# VoltageBooster48V.net
KiCad netlist of a schematic drawn in Altium Designer
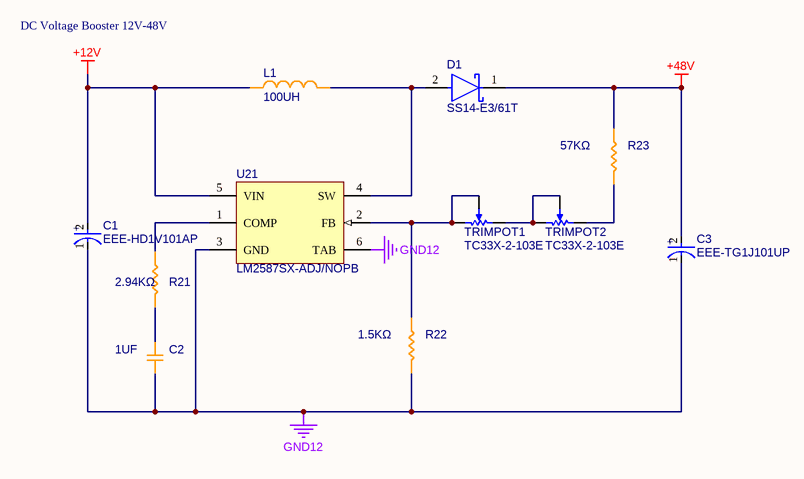
[diagram p0: VoltageBooster48V.SchDoc]

(export (version "E")
  (design (tool "Eeschema 10.0.6"))
  (components
    (comp (ref "C1")
      (value "EEE-HD1V101AP")
      (footprint "FP-HDG-MFG")
      (fields (field (name "VOLTAGE") "35V") (field (name "TOLERANCE") "20%"))
      (libsource (lib "Altium Content Vault") (part "203bc49f2ac43e59fd269a8c329ed05"))
    )
    (comp (ref "C2")
      (value "1UF")
      (footprint "CAP_0603")
      (description "Capacitor SMD 0603 generic")
      (libsource (lib "GenericRC") (part "CAP_0603"))
    )
    (comp (ref "C3")
      (value "EEE-TG1J101UP")
      (footprint "FP-TGG-MFG")
      (description "CAP ALUM 100UF 20% 63V SMD")
      (fields (field (name "VOLTAGE") "63V") (field (name "TOLERANCE") "20%"))
      (libsource (lib "Altium Content Vault") (part "203bc49f2ac43e59fd269a8c329ed05"))
    )
    (comp (ref "D1")
      (value "SS14-E3/61T")
      (footprint "FP-95400-MFG")
      (description "DIODE SCHOTTKY 40V 1A DO214AC")
      (fields
        (field (name "OCTOPART") "https://octopart.com/ss14-e3%2F61t-vishay-39552847")
        (field (name "MANUFACTURER") "Vishay")
      )
      (libsource (lib "Altium Content Vault") (part "1d6ec82d83fb6aee721767c19dac4b9"))
    )
    (comp (ref "L1")
      (value "100UH")
      (footprint "IND_Boost")
      (description "Voltage Boost Inductor")
      (libsource (lib "GenericRC") (part "Boost Inductor"))
    )
    (comp (ref "R21")
      (value "2.94KΩ")
      (footprint "RES_0603")
      (description "Resistor SMD 0603 generic")
      (libsource (lib "GenericRC") (part "RES_0603"))
    )
    (comp (ref "R22")
      (value "1.5KΩ")
      (footprint "RES_0603")
      (description "Resistor SMD 0603 generic")
      (libsource (lib "GenericRC") (part "RES_0603"))
    )
    (comp (ref "R23")
      (value "57KΩ")
      (footprint "RES_0603")
      (description "Resistor SMD 0603 generic")
      (libsource (lib "GenericRC") (part "RES_0603"))
    )
    (comp (ref "TRIMPOT1")
      (value "TC33X-2-103E")
      (footprint "BOUR-TC33X-2_V")
      (description "Trimming Potentiometer, 10000 Ohm, -40 to 100 degC, 3-Pin SMD, RoHS, Tape and Reel")
      (fields (field (name "TOLERANCE") "25%") (field (name "MANUFACTURER") "Bourns"))
      (libsource (lib "Altium Content Vault") (part "RES-ADJ-3_A"))
    )
    (comp (ref "TRIMPOT2")
      (value "TC33X-2-103E")
      (footprint "BOUR-TC33X-2_V")
      (description "Trimming Potentiometer, 10000 Ohm, -40 to 100 degC, 3-Pin SMD, RoHS, Tape and Reel")
      (fields (field (name "TOLERANCE") "25%") (field (name "MANUFACTURER") "Bourns"))
      (libsource (lib "Altium Content Vault") (part "RES-ADJ-3_A"))
    )
    (comp (ref "U21")
      (value "LM2587SX-ADJ/NOPB")
      (footprint "KTT0005B_N")
      (description "5A Flyback Regulator, 5-pin TO-263, Pb-Free")
      (fields (field (name "MANUFACTURER") "Texas Instruments"))
      (libsource (lib "Altium Content Vault") (part "PM-SWREG-LM2585S-12"))
    )
  )
  (nets
    (net (code "1") (name "+12V") (class "Default")
      (node (ref "C1") (pin "2") (pinfunction "A_2") (pintype "passive"))
      (node (ref "L1") (pin "1") (pintype "passive"))
      (node (ref "U21") (pin "5") (pinfunction "VIN_5") (pintype "power_in"))
    )
    (net (code "2") (name "+48V") (class "Default")
      (node (ref "C3") (pin "2") (pinfunction "A_2") (pintype "passive"))
      (node (ref "D1") (pin "1") (pinfunction "C_1") (pintype "passive"))
      (node (ref "R23") (pin "2") (pintype "passive"))
    )
    (net (code "3") (name "GND12") (class "Default")
      (node (ref "C1") (pin "1") (pinfunction "C_1") (pintype "passive"))
      (node (ref "C2") (pin "1") (pintype "passive"))
      (node (ref "C3") (pin "1") (pinfunction "C_1") (pintype "passive"))
      (node (ref "R22") (pin "1") (pintype "passive"))
      (node (ref "U21") (pin "3") (pinfunction "GND_3") (pintype "power_in"))
      (node (ref "U21") (pin "6") (pinfunction "TAB_6") (pintype "passive"))
    )
    (net (code "4") (name "Net-(C2-Pad2)") (class "Default")
      (node (ref "C2") (pin "2") (pintype "passive"))
      (node (ref "R21") (pin "1") (pintype "passive"))
    )
    (net (code "5") (name "Net-(D1-A)") (class "Default")
      (node (ref "D1") (pin "2") (pinfunction "A_2") (pintype "passive"))
      (node (ref "L1") (pin "2") (pintype "passive"))
      (node (ref "U21") (pin "4") (pinfunction "SW_4") (pintype "power_in"))
    )
    (net (code "6") (name "Net-(R23-Pad1)") (class "Default")
      (node (ref "R23") (pin "1") (pintype "passive"))
      (node (ref "TRIMPOT2") (pin "3") (pinfunction "3_3") (pintype "passive"))
    )
    (net (code "7") (name "Net-(TRIMPOT1-Pad3)") (class "Default")
      (node (ref "TRIMPOT1") (pin "3") (pinfunction "3_3") (pintype "passive"))
      (node (ref "TRIMPOT2") (pin "1") (pinfunction "1_1") (pintype "passive"))
      (node (ref "TRIMPOT2") (pin "2") (pinfunction "2_2") (pintype "passive"))
    )
    (net (code "8") (name "Net-(U21-COMP)") (class "Default")
      (node (ref "R21") (pin "2") (pintype "passive"))
      (node (ref "U21") (pin "1") (pinfunction "COMP_1") (pintype "passive"))
    )
    (net (code "9") (name "Net-(U21-FB)") (class "Default")
      (node (ref "R22") (pin "2") (pintype "passive"))
      (node (ref "TRIMPOT1") (pin "1") (pinfunction "1_1") (pintype "passive"))
      (node (ref "TRIMPOT1") (pin "2") (pinfunction "2_2") (pintype "passive"))
      (node (ref "U21") (pin "2") (pinfunction "FB_2") (pintype "input"))
    )
  )
)
